# Usb_To_UART.net
KiCad netlist of a schematic drawn in Altium Designer
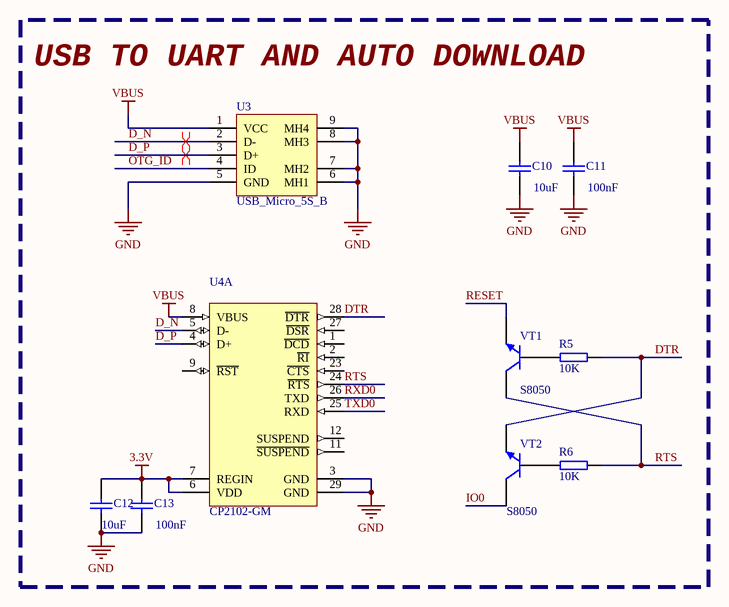
[diagram p0: Usb_To_UART.SchDoc]

(export (version "E")
  (design (tool "Eeschema 10.0.6"))
  (components
    (comp (ref "C10")
      (value "10uF")
      (footprint "SMT0603")
      (description "CAP SM 0603 X5R 10uF 10%")
      (fields (field (name "TOLERANCE") "±10%") (field (name "Comment") "Cap Semi"))
      (libsource (lib "electronpowered") (part "CAP-SM-0603-X5R-10uF"))
    )
    (comp (ref "C11")
      (value "100nF")
      (footprint "SMT0603")
      (description "CAP SM 0603 X7R 100nF 10%")
      (fields (field (name "TOLERANCE") "±10%") (field (name "Comment") "Cap Semi"))
      (libsource (lib "electronpowered") (part "CAP-SM-0603-X7R-100nF"))
    )
    (comp (ref "C12")
      (value "10uF")
      (footprint "SMT0603")
      (description "CAP SM 0603 X5R 10uF 10%")
      (fields (field (name "TOLERANCE") "±10%") (field (name "Comment") "Cap Semi"))
      (libsource (lib "electronpowered") (part "CAP-SM-0603-X5R-10uF"))
    )
    (comp (ref "C13")
      (value "100nF")
      (footprint "SMT0603")
      (description "CAP SM 0603 X7R 100nF 10%")
      (fields (field (name "TOLERANCE") "±10%") (field (name "Comment") "Cap Semi"))
      (libsource (lib "electronpowered") (part "CAP-SM-0603-X7R-100nF"))
    )
    (comp (ref "R5")
      (value "10K")
      (footprint "SMT0603")
      (description "RES SM 0603 10K")
      (fields (field (name "Comment") "Resistor"))
      (libsource (lib "electronpowered") (part "RES-SM-0603-10K"))
    )
    (comp (ref "R6")
      (value "10K")
      (footprint "SMT0603")
      (description "RES SM 0603 10K")
      (fields (field (name "Comment") "Resistor"))
      (libsource (lib "electronpowered") (part "RES-SM-0603-10K"))
    )
    (comp (ref "U3")
      (value "USB_Micro_5S_B")
      (footprint "USB_MICRO_5S_B")
      (description "USB micro female SMT with 4 fixed foot")
      (libsource (lib "NODEMCU_DEVKIT_V1.0") (part "USB_Micro_5S_B"))
    )
    (comp (ref "U4")
      (value "CP2102-GM")
      (footprint "CP2102")
      (description "Single-Chip USB to UART Bridge, 1024 Bytes EEPROM, -40 to 85 degC, 28-pin QFN, Tube")
      (fields (field (name "MANUFACTURER") "Silicon Labs"))
      (libsource (lib "Silicon Labs Interface") (part "CP2102-GM"))
    )
    (comp (ref "VT1")
      (value "S8050")
      (footprint "SMT_TRIODE_NPN")
      (description "Surface mount NPN transistor, package SOT-23")
      (libsource (lib "NODEMCU_DEVKIT_V1.0") (part "SMT_TRIODE_NPN"))
    )
    (comp (ref "VT2")
      (value "S8050")
      (footprint "SMT_TRIODE_NPN")
      (description "Surface mount NPN transistor, package SOT-23")
      (libsource (lib "NODEMCU_DEVKIT_V1.0") (part "SMT_TRIODE_NPN"))
    )
  )
  (nets
    (net (code "1") (name "/DTR") (class "Default")
      (node (ref "R5") (pin "1") (pinfunction "1_1") (pintype "passive"))
      (node (ref "U4") (pin "28") (pinfunction "~{DTR}_28") (pintype "output"))
      (node (ref "VT2") (pin "2") (pinfunction "E_2") (pintype "passive"))
    )
    (net (code "2") (name "/D_N") (class "Default")
      (node (ref "U3") (pin "2") (pinfunction "D-_2") (pintype "passive"))
      (node (ref "U4") (pin "5") (pinfunction "D-_5") (pintype "bidirectional"))
    )
    (net (code "3") (name "/D_P") (class "Default")
      (node (ref "U3") (pin "3") (pinfunction "D+_3") (pintype "passive"))
      (node (ref "U4") (pin "4") (pinfunction "D+_4") (pintype "bidirectional"))
    )
    (net (code "4") (name "/IO0") (class "Default")
      (node (ref "VT2") (pin "3") (pinfunction "C_3") (pintype "passive"))
    )
    (net (code "5") (name "/OTG_ID") (class "Default")
      (node (ref "U3") (pin "4") (pinfunction "ID_4") (pintype "passive"))
    )
    (net (code "6") (name "/RESET") (class "Default")
      (node (ref "VT1") (pin "2") (pinfunction "E_2") (pintype "passive"))
    )
    (net (code "7") (name "/RTS") (class "Default")
      (node (ref "R6") (pin "1") (pinfunction "1_1") (pintype "passive"))
      (node (ref "U4") (pin "24") (pinfunction "~{RTS}_24") (pintype "output"))
      (node (ref "VT1") (pin "3") (pinfunction "C_3") (pintype "passive"))
    )
    (net (code "8") (name "/RXD0") (class "Default")
      (node (ref "U4") (pin "26") (pinfunction "TXD_26") (pintype "output"))
    )
    (net (code "9") (name "/TXD0") (class "Default")
      (node (ref "U4") (pin "25") (pinfunction "RXD_25") (pintype "input"))
    )
    (net (code "10") (name "3.3V") (class "Default")
      (node (ref "C12") (pin "2") (pinfunction "2_2") (pintype "passive"))
      (node (ref "C13") (pin "2") (pinfunction "2_2") (pintype "passive"))
      (node (ref "U4") (pin "6") (pinfunction "VDD_6") (pintype "power_in"))
      (node (ref "U4") (pin "7") (pinfunction "REGIN_7") (pintype "power_in"))
    )
    (net (code "11") (name "GND") (class "Default")
      (node (ref "C10") (pin "1") (pinfunction "1_1") (pintype "passive"))
      (node (ref "C11") (pin "1") (pinfunction "1_1") (pintype "passive"))
      (node (ref "C12") (pin "1") (pinfunction "1_1") (pintype "passive"))
      (node (ref "C13") (pin "1") (pinfunction "1_1") (pintype "passive"))
      (node (ref "U3") (pin "5") (pinfunction "GND_5") (pintype "passive"))
      (node (ref "U3") (pin "6") (pinfunction "MH1_6") (pintype "passive"))
      (node (ref "U3") (pin "7") (pinfunction "MH2_7") (pintype "passive"))
      (node (ref "U3") (pin "8") (pinfunction "MH3_8") (pintype "passive"))
      (node (ref "U3") (pin "9") (pinfunction "MH4_9") (pintype "passive"))
      (node (ref "U4") (pin "29") (pinfunction "GND_29") (pintype "power_in"))
      (node (ref "U4") (pin "3") (pinfunction "GND_3") (pintype "power_in"))
    )
    (net (code "12") (name "Net-(VT1-B)") (class "Default")
      (node (ref "R5") (pin "2") (pinfunction "2_2") (pintype "passive"))
      (node (ref "VT1") (pin "1") (pinfunction "B_1") (pintype "passive"))
    )
    (net (code "13") (name "Net-(VT2-B)") (class "Default")
      (node (ref "R6") (pin "2") (pinfunction "2_2") (pintype "passive"))
      (node (ref "VT2") (pin "1") (pinfunction "B_1") (pintype "passive"))
    )
    (net (code "14") (name "VBUS") (class "Default")
      (node (ref "C10") (pin "2") (pinfunction "2_2") (pintype "passive"))
      (node (ref "C11") (pin "2") (pinfunction "2_2") (pintype "passive"))
      (node (ref "U3") (pin "1") (pinfunction "VCC_1") (pintype "passive"))
      (node (ref "U4") (pin "8") (pinfunction "VBUS_8") (pintype "input"))
    )
    (net (code "15") (name "unconnected-(U4A-SUSPEND-Pad12)") (class "Default")
      (node (ref "U4") (pin "12") (pinfunction "SUSPEND_12") (pintype "output"))
    )
    (net (code "16") (name "unconnected-(U4A-~{CTS}-Pad23)") (class "Default")
      (node (ref "U4") (pin "23") (pinfunction "~{CTS}_23") (pintype "input"))
    )
    (net (code "17") (name "unconnected-(U4A-~{DCD}-Pad1)") (class "Default")
      (node (ref "U4") (pin "1") (pinfunction "~{DCD}_1") (pintype "input"))
    )
    (net (code "18") (name "unconnected-(U4A-~{DSR}-Pad27)") (class "Default")
      (node (ref "U4") (pin "27") (pinfunction "~{DSR}_27") (pintype "input"))
    )
    (net (code "19") (name "unconnected-(U4A-~{RI}-Pad2)") (class "Default")
      (node (ref "U4") (pin "2") (pinfunction "~{RI}_2") (pintype "input"))
    )
    (net (code "20") (name "unconnected-(U4A-~{RST}-Pad9)") (class "Default")
      (node (ref "U4") (pin "9") (pinfunction "~{RST}_9") (pintype "bidirectional"))
    )
    (net (code "21") (name "unconnected-(U4A-~{SUSPEND}-Pad11)") (class "Default")
      (node (ref "U4") (pin "11") (pinfunction "~{SUSPEND}_11") (pintype "output"))
    )
  )
)
